# LD_driver.net
KiCad netlist of a schematic drawn in Altium Designer
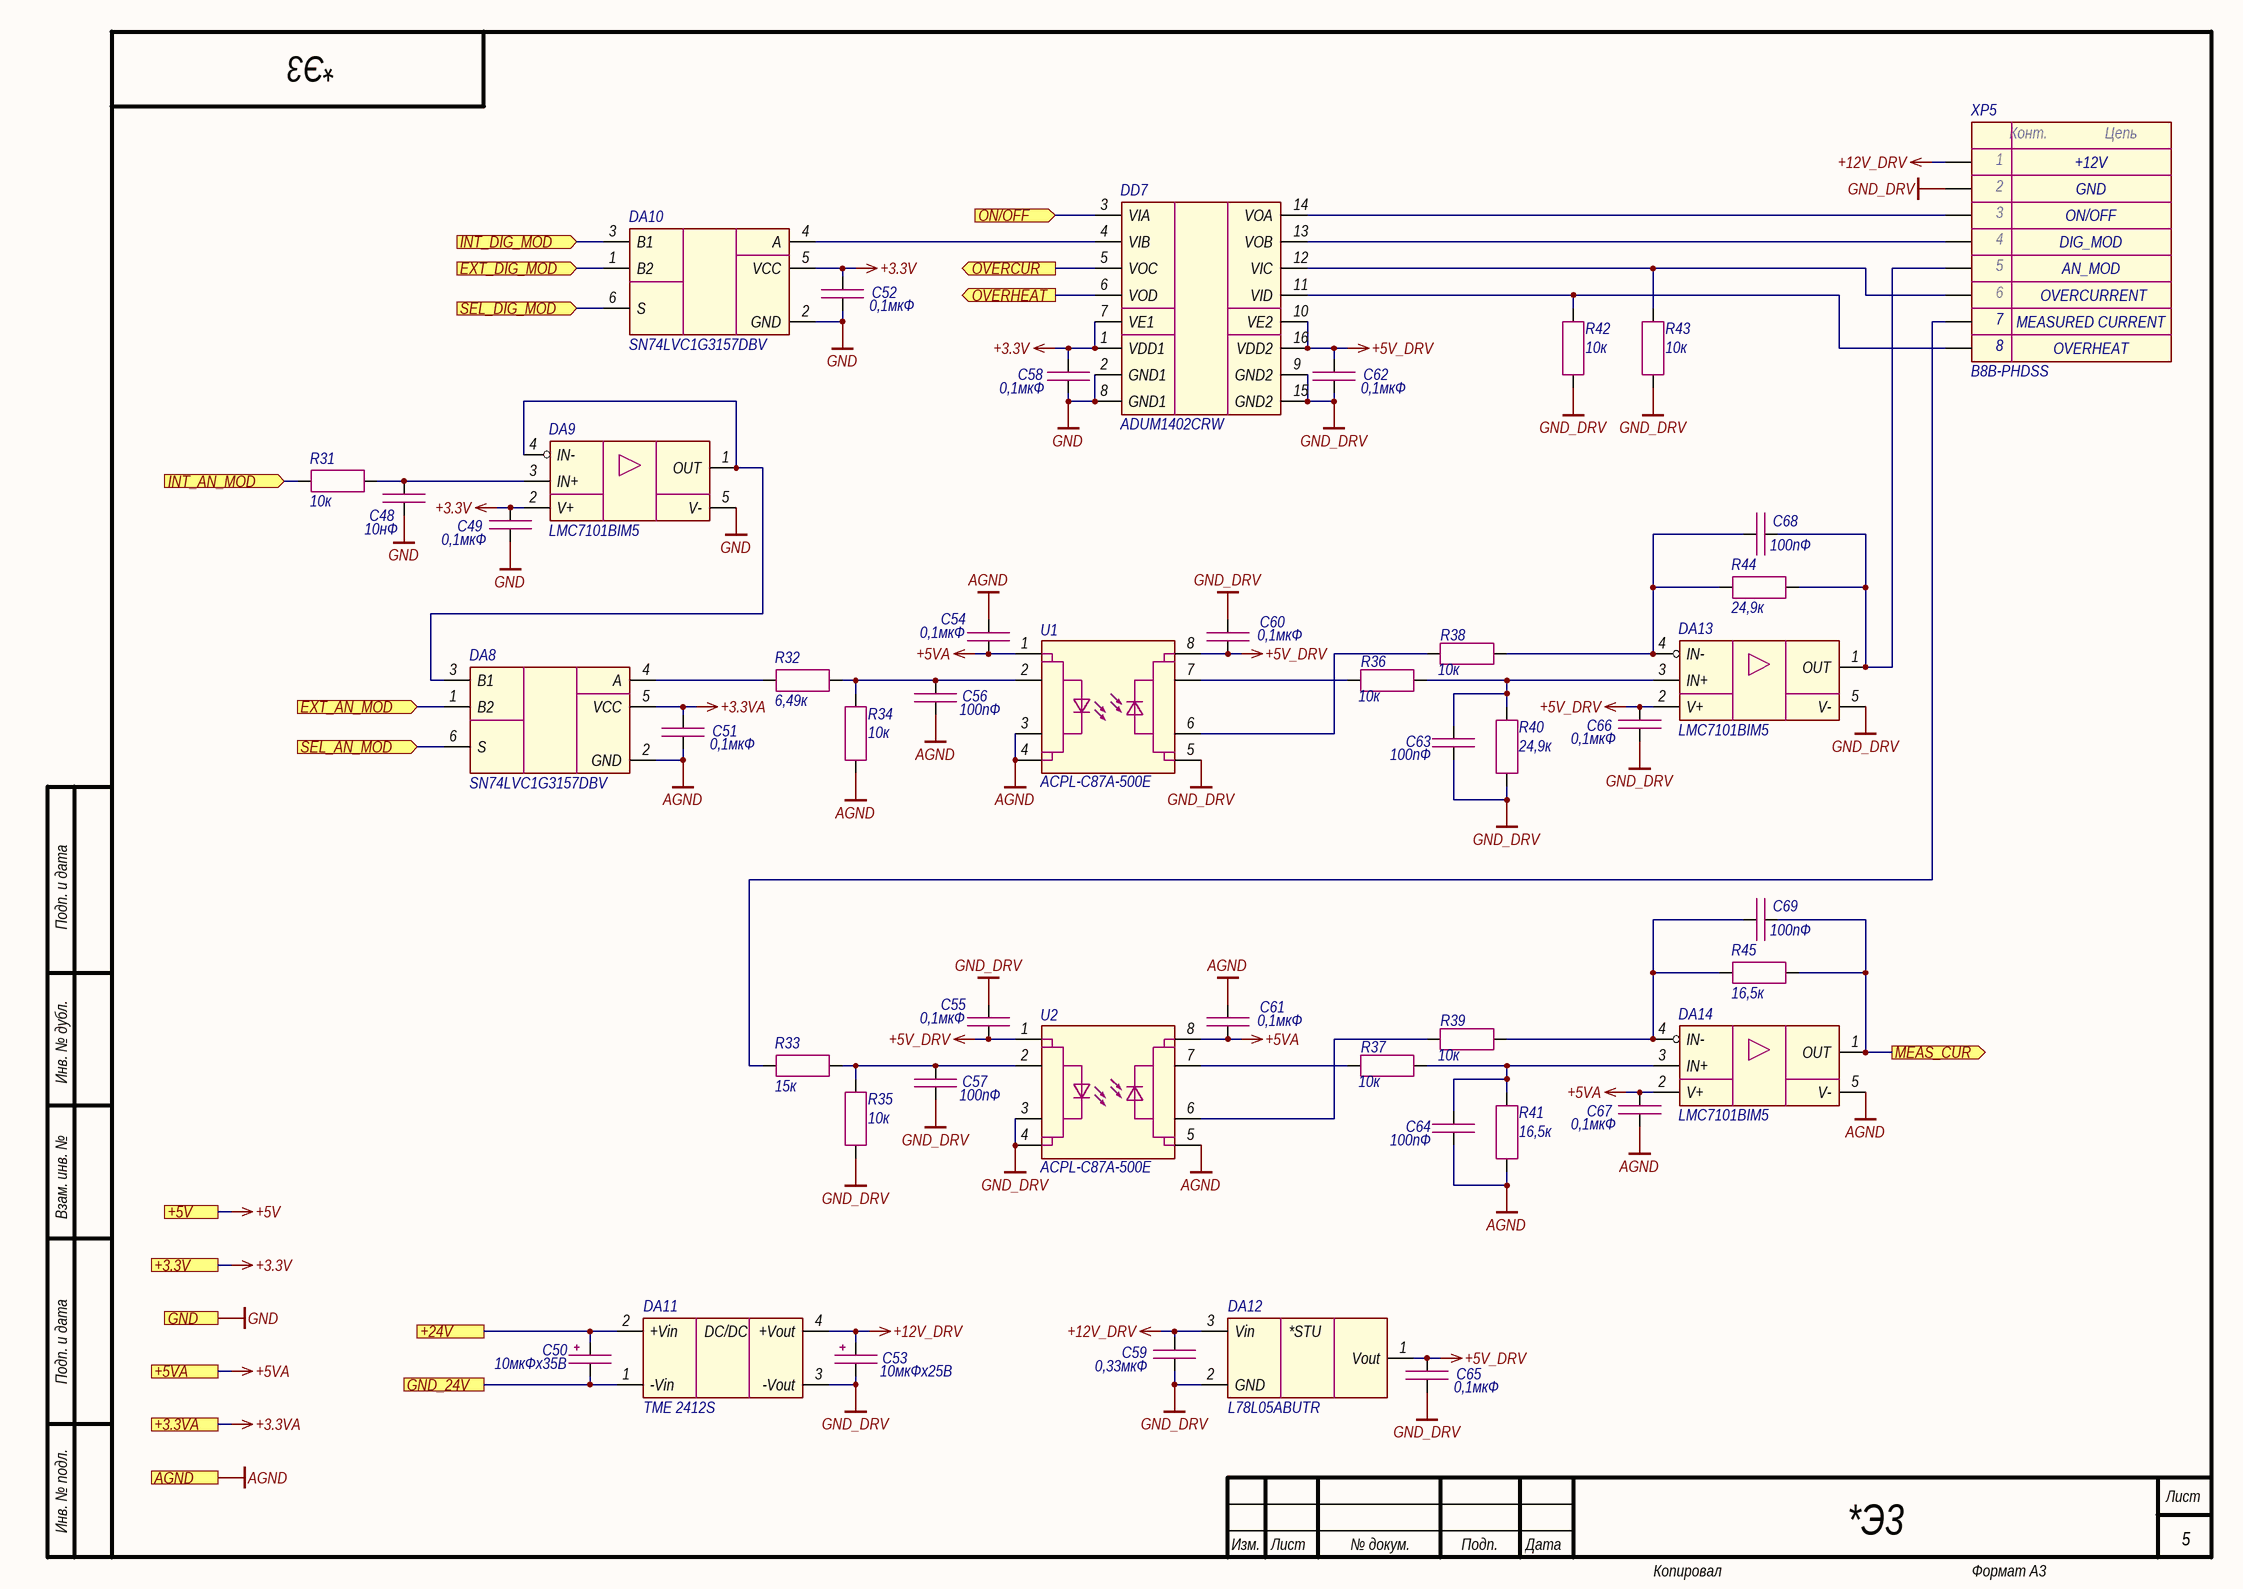
[diagram p0: LD_driver.SchDoc]

(export (version "E")
  (design (tool "Eeschema 10.0.6"))
  (components
    (comp (ref "C48")
      (value "10нФ")
      (footprint "Pcb_library:CAP_0603")
      (fields (field (name "MANUFACTURER") "Murata"))
      (libsource (lib "Schem_library") (part "Capacitor"))
    )
    (comp (ref "C49")
      (value "0,1мкФ")
      (footprint "Pcb_library:CAP_0603")
      (fields (field (name "MANUFACTURER") "Murata"))
      (libsource (lib "Schem_library") (part "Capacitor"))
    )
    (comp (ref "C50")
      (value "10мкФх35B")
      (footprint "Pcb_library:CAP_C")
      (libsource (lib "Schem_library") (part "Capacitor_Polar"))
    )
    (comp (ref "C51")
      (value "0,1мкФ")
      (footprint "Pcb_library:CAP_0603")
      (fields (field (name "MANUFACTURER") "Murata"))
      (libsource (lib "Schem_library") (part "Capacitor"))
    )
    (comp (ref "C52")
      (value "0,1мкФ")
      (footprint "Pcb_library:CAP_0603")
      (fields (field (name "MANUFACTURER") "Murata"))
      (libsource (lib "Schem_library") (part "Capacitor"))
    )
    (comp (ref "C53")
      (value "10мкФх25B")
      (footprint "Pcb_library:CAP_C")
      (libsource (lib "Schem_library") (part "Capacitor_Polar"))
    )
    (comp (ref "C54")
      (value "0,1мкФ")
      (footprint "Pcb_library:CAP_0603")
      (fields (field (name "MANUFACTURER") "Murata"))
      (libsource (lib "Schem_library") (part "Capacitor"))
    )
    (comp (ref "C55")
      (value "0,1мкФ")
      (footprint "Pcb_library:CAP_0603")
      (fields (field (name "MANUFACTURER") "Murata"))
      (libsource (lib "Schem_library") (part "Capacitor"))
    )
    (comp (ref "C56")
      (value "100пФ")
      (footprint "Pcb_library:CAP_0603")
      (fields (field (name "MANUFACTURER") "Murata"))
      (libsource (lib "Schem_library") (part "Capacitor"))
    )
    (comp (ref "C57")
      (value "100пФ")
      (footprint "Pcb_library:CAP_0603")
      (fields (field (name "MANUFACTURER") "Murata"))
      (libsource (lib "Schem_library") (part "Capacitor"))
    )
    (comp (ref "C58")
      (value "0,1мкФ")
      (footprint "Pcb_library:CAP_0603")
      (fields (field (name "MANUFACTURER") "Murata"))
      (libsource (lib "Schem_library") (part "Capacitor"))
    )
    (comp (ref "C59")
      (value "0,33мкФ")
      (footprint "Pcb_library:CAP_0805")
      (fields (field (name "MANUFACTURER") "Murata"))
      (libsource (lib "Schem_library") (part "Capacitor"))
    )
    (comp (ref "C60")
      (value "0,1мкФ")
      (footprint "Pcb_library:CAP_0603")
      (fields (field (name "MANUFACTURER") "Murata"))
      (libsource (lib "Schem_library") (part "Capacitor"))
    )
    (comp (ref "C61")
      (value "0,1мкФ")
      (footprint "Pcb_library:CAP_0603")
      (fields (field (name "MANUFACTURER") "Murata"))
      (libsource (lib "Schem_library") (part "Capacitor"))
    )
    (comp (ref "C62")
      (value "0,1мкФ")
      (footprint "Pcb_library:CAP_0603")
      (fields (field (name "MANUFACTURER") "Murata"))
      (libsource (lib "Schem_library") (part "Capacitor"))
    )
    (comp (ref "C63")
      (value "100пФ")
      (footprint "Pcb_library:CAP_0603")
      (fields (field (name "MANUFACTURER") "Murata"))
      (libsource (lib "Schem_library") (part "Capacitor"))
    )
    (comp (ref "C64")
      (value "100пФ")
      (footprint "Pcb_library:CAP_0603")
      (fields (field (name "MANUFACTURER") "Murata"))
      (libsource (lib "Schem_library") (part "Capacitor"))
    )
    (comp (ref "C65")
      (value "0,1мкФ")
      (footprint "Pcb_library:CAP_0603")
      (fields (field (name "MANUFACTURER") "Murata"))
      (libsource (lib "Schem_library") (part "Capacitor"))
    )
    (comp (ref "C66")
      (value "0,1мкФ")
      (footprint "Pcb_library:CAP_0603")
      (fields (field (name "MANUFACTURER") "Murata"))
      (libsource (lib "Schem_library") (part "Capacitor"))
    )
    (comp (ref "C67")
      (value "0,1мкФ")
      (footprint "Pcb_library:CAP_0603")
      (fields (field (name "MANUFACTURER") "Murata"))
      (libsource (lib "Schem_library") (part "Capacitor"))
    )
    (comp (ref "C68")
      (value "100пФ")
      (footprint "Pcb_library:CAP_0603")
      (fields (field (name "MANUFACTURER") "Murata"))
      (libsource (lib "Schem_library") (part "Capacitor"))
    )
    (comp (ref "C69")
      (value "100пФ")
      (footprint "Pcb_library:CAP_0603")
      (fields (field (name "MANUFACTURER") "Murata"))
      (libsource (lib "Schem_library") (part "Capacitor"))
    )
    (comp (ref "DA8")
      (value "SN74LVC1G3157DBV")
      (footprint "Pcb_library:SOT-23-6")
      (fields (field (name "MANUFACTURER") "Texas Instruments"))
      (libsource (lib "Schem_library") (part "SN74LVC1G3157"))
    )
    (comp (ref "DA9")
      (value "LMC7101BIM5")
      (footprint "Pcb_library:SOT-23-5")
      (fields (field (name "MANUFACTURER") "Texas Instruments"))
      (libsource (lib "Schem_library") (part "LMC7101"))
    )
    (comp (ref "DA10")
      (value "SN74LVC1G3157DBV")
      (footprint "Pcb_library:SOT-23-6")
      (fields (field (name "MANUFACTURER") "Texas Instruments"))
      (libsource (lib "Schem_library") (part "SN74LVC1G3157"))
    )
    (comp (ref "DA11")
      (value "TME 2412S")
      (footprint "Pcb_library:TME (SIP-4)")
      (fields (field (name "MANUFACTURER") "Traco Power"))
      (libsource (lib "Schem_library") (part "TME"))
    )
    (comp (ref "DA12")
      (value "L78L05ABUTR")
      (footprint "Pcb_library:SOT-89")
      (fields (field (name "MANUFACTURER") "STMicroelectronics"))
      (libsource (lib "Schem_library") (part "LD2981ABU50TR"))
    )
    (comp (ref "DA13")
      (value "LMC7101BIM5")
      (footprint "Pcb_library:SOT-23-5")
      (fields (field (name "MANUFACTURER") "Texas Instruments"))
      (libsource (lib "Schem_library") (part "LMC7101"))
    )
    (comp (ref "DA14")
      (value "LMC7101BIM5")
      (footprint "Pcb_library:SOT-23-5")
      (fields (field (name "MANUFACTURER") "Texas Instruments"))
      (libsource (lib "Schem_library") (part "LMC7101"))
    )
    (comp (ref "DD7")
      (value "ADUM1402CRW")
      (footprint "Pcb_library:SOIC-16W")
      (fields (field (name "MANUFACTURER") "Analog Devices"))
      (libsource (lib "Schem_library") (part "ADUM1402"))
    )
    (comp (ref "R31")
      (value "10к")
      (footprint "Pcb_library:RES_0603")
      (fields (field (name "MANUFACTURER") "Yageo"))
      (libsource (lib "Schem_library") (part "Resistor"))
    )
    (comp (ref "R32")
      (value "6,49к")
      (footprint "Pcb_library:RES_0603")
      (fields (field (name "MANUFACTURER") "Yageo"))
      (libsource (lib "Schem_library") (part "Resistor"))
    )
    (comp (ref "R33")
      (value "15к")
      (footprint "Pcb_library:RES_0603")
      (fields (field (name "MANUFACTURER") "Yageo"))
      (libsource (lib "Schem_library") (part "Resistor"))
    )
    (comp (ref "R34")
      (value "10к")
      (footprint "Pcb_library:RES_0603")
      (fields (field (name "MANUFACTURER") "Yageo"))
      (libsource (lib "Schem_library") (part "Resistor"))
    )
    (comp (ref "R35")
      (value "10к")
      (footprint "Pcb_library:RES_0603")
      (fields (field (name "MANUFACTURER") "Yageo"))
      (libsource (lib "Schem_library") (part "Resistor"))
    )
    (comp (ref "R36")
      (value "10к")
      (footprint "Pcb_library:RES_0603")
      (fields (field (name "MANUFACTURER") "Yageo"))
      (libsource (lib "Schem_library") (part "Resistor"))
    )
    (comp (ref "R37")
      (value "10к")
      (footprint "Pcb_library:RES_0603")
      (fields (field (name "MANUFACTURER") "Yageo"))
      (libsource (lib "Schem_library") (part "Resistor"))
    )
    (comp (ref "R38")
      (value "10к")
      (footprint "Pcb_library:RES_0603")
      (fields (field (name "MANUFACTURER") "Yageo"))
      (libsource (lib "Schem_library") (part "Resistor"))
    )
    (comp (ref "R39")
      (value "10к")
      (footprint "Pcb_library:RES_0603")
      (fields (field (name "MANUFACTURER") "Yageo"))
      (libsource (lib "Schem_library") (part "Resistor"))
    )
    (comp (ref "R40")
      (value "24,9к")
      (footprint "Pcb_library:RES_0603")
      (fields (field (name "MANUFACTURER") "Yageo"))
      (libsource (lib "Schem_library") (part "Resistor"))
    )
    (comp (ref "R41")
      (value "16,5к")
      (footprint "Pcb_library:RES_0603")
      (fields (field (name "MANUFACTURER") "Yageo"))
      (libsource (lib "Schem_library") (part "Resistor"))
    )
    (comp (ref "R42")
      (value "10к")
      (footprint "Pcb_library:RES_0603")
      (fields (field (name "MANUFACTURER") "Yageo"))
      (libsource (lib "Schem_library") (part "Resistor"))
    )
    (comp (ref "R43")
      (value "10к")
      (footprint "Pcb_library:RES_0603")
      (fields (field (name "MANUFACTURER") "Yageo"))
      (libsource (lib "Schem_library") (part "Resistor"))
    )
    (comp (ref "R44")
      (value "24,9к")
      (footprint "Pcb_library:RES_0603")
      (fields (field (name "MANUFACTURER") "Yageo"))
      (libsource (lib "Schem_library") (part "Resistor"))
    )
    (comp (ref "R45")
      (value "16,5к")
      (footprint "Pcb_library:RES_0603")
      (fields (field (name "MANUFACTURER") "Yageo"))
      (libsource (lib "Schem_library") (part "Resistor"))
    )
    (comp (ref "U1")
      (value "ACPL-C87A-500E")
      (footprint "Pcb_library:SSO-8")
      (fields (field (name "MANUFACTURER") "Broadcom"))
      (libsource (lib "Schem_library") (part "ACPL-C87"))
    )
    (comp (ref "U2")
      (value "ACPL-C87A-500E")
      (footprint "Pcb_library:SSO-8")
      (fields (field (name "MANUFACTURER") "Broadcom"))
      (libsource (lib "Schem_library") (part "ACPL-C87"))
    )
    (comp (ref "XP5")
      (value "B8B-PHDSS")
      (footprint "Pcb_library:B8B-PHDSS")
      (fields (field (name "MANUFACTURER") "JST"))
      (libsource (lib "Schem_library") (part "Connector-8"))
    )
  )
  (nets
    (net (code "1") (name "+3.3V") (class "Default")
      (node (ref "C49") (pin "1") (pinfunction "1_1") (pintype "passive"))
      (node (ref "C52") (pin "1") (pinfunction "1_1") (pintype "passive"))
      (node (ref "C58") (pin "1") (pinfunction "1_1") (pintype "passive"))
      (node (ref "DA10") (pin "5") (pinfunction "VCC_5") (pintype "passive"))
      (node (ref "DA9") (pin "2") (pinfunction "V+_2") (pintype "passive"))
      (node (ref "DD7") (pin "1") (pinfunction "VDD1_1") (pintype "passive"))
      (node (ref "DD7") (pin "7") (pinfunction "VE1_7") (pintype "passive"))
    )
    (net (code "2") (name "+3.3VA") (class "Default")
      (node (ref "C51") (pin "1") (pinfunction "1_1") (pintype "passive"))
      (node (ref "DA8") (pin "5") (pinfunction "VCC_5") (pintype "passive"))
    )
    (net (code "4") (name "+5VA") (class "Default")
      (node (ref "C54") (pin "1") (pinfunction "1_1") (pintype "passive"))
      (node (ref "C61") (pin "1") (pinfunction "1_1") (pintype "passive"))
      (node (ref "C67") (pin "1") (pinfunction "1_1") (pintype "passive"))
      (node (ref "DA14") (pin "2") (pinfunction "V+_2") (pintype "passive"))
      (node (ref "U1") (pin "1") (pinfunction "VDD1_1") (pintype "passive"))
      (node (ref "U2") (pin "8") (pinfunction "VDD2_8") (pintype "passive"))
    )
    (net (code "5") (name "+5V_DRV") (class "Default")
      (node (ref "C55") (pin "1") (pinfunction "1_1") (pintype "passive"))
      (node (ref "C60") (pin "1") (pinfunction "1_1") (pintype "passive"))
      (node (ref "C62") (pin "1") (pinfunction "1_1") (pintype "passive"))
      (node (ref "C65") (pin "1") (pinfunction "1_1") (pintype "passive"))
      (node (ref "C66") (pin "1") (pinfunction "1_1") (pintype "passive"))
      (node (ref "DA12") (pin "1") (pinfunction "Vout_1") (pintype "passive"))
      (node (ref "DA13") (pin "2") (pinfunction "V+_2") (pintype "passive"))
      (node (ref "DD7") (pin "10") (pinfunction "VE2_10") (pintype "passive"))
      (node (ref "DD7") (pin "16") (pinfunction "VDD2_16") (pintype "passive"))
      (node (ref "U1") (pin "8") (pinfunction "VDD2_8") (pintype "passive"))
      (node (ref "U2") (pin "1") (pinfunction "VDD1_1") (pintype "passive"))
    )
    (net (code "6") (name "+12V_DRV") (class "Default")
      (node (ref "C53") (pin "1") (pinfunction "1_1") (pintype "passive"))
      (node (ref "C59") (pin "2") (pinfunction "2_2") (pintype "passive"))
      (node (ref "DA11") (pin "4") (pinfunction "+Vout_4") (pintype "passive"))
      (node (ref "DA12") (pin "3") (pinfunction "Vin_3") (pintype "passive"))
      (node (ref "XP5") (pin "1") (pintype "passive"))
    )
    (net (code "7") (name "/+24V") (class "Default")
      (node (ref "C50") (pin "1") (pinfunction "1_1") (pintype "passive"))
      (node (ref "DA11") (pin "2") (pinfunction "+Vin_2") (pintype "passive"))
    )
    (net (code "8") (name "/EXT_AN_MOD") (class "Default")
      (node (ref "DA8") (pin "1") (pinfunction "B2_1") (pintype "passive"))
    )
    (net (code "9") (name "/EXT_DIG_MOD") (class "Default")
      (node (ref "DA10") (pin "1") (pinfunction "B2_1") (pintype "passive"))
    )
    (net (code "10") (name "/GND_24V") (class "Default")
      (node (ref "C50") (pin "2") (pinfunction "2_2") (pintype "passive"))
      (node (ref "DA11") (pin "1") (pinfunction "-Vin_1") (pintype "passive"))
    )
    (net (code "11") (name "/INT_AN_MOD") (class "Default")
      (node (ref "R31") (pin "1") (pinfunction "1_1") (pintype "passive"))
    )
    (net (code "12") (name "/INT_DIG_MOD") (class "Default")
      (node (ref "DA10") (pin "3") (pinfunction "B1_3") (pintype "passive"))
    )
    (net (code "13") (name "/MEAS_CUR") (class "Default")
      (node (ref "C69") (pin "2") (pinfunction "2_2") (pintype "passive"))
      (node (ref "DA14") (pin "1") (pinfunction "OUT_1") (pintype "passive"))
      (node (ref "R45") (pin "1") (pinfunction "1_1") (pintype "passive"))
    )
    (net (code "14") (name "/ON{slash}OFF") (class "Default")
      (node (ref "DD7") (pin "3") (pinfunction "VIA_3") (pintype "passive"))
    )
    (net (code "15") (name "/OVERCUR") (class "Default")
      (node (ref "DD7") (pin "5") (pinfunction "VOC_5") (pintype "passive"))
    )
    (net (code "16") (name "/OVERHEAT") (class "Default")
      (node (ref "DD7") (pin "6") (pinfunction "VOD_6") (pintype "passive"))
    )
    (net (code "17") (name "/SEL_AN_MOD") (class "Default")
      (node (ref "DA8") (pin "6") (pinfunction "S_6") (pintype "passive"))
    )
    (net (code "18") (name "/SEL_DIG_MOD") (class "Default")
      (node (ref "DA10") (pin "6") (pinfunction "S_6") (pintype "passive"))
    )
    (net (code "19") (name "AGND") (class "Default")
      (node (ref "C51") (pin "2") (pinfunction "2_2") (pintype "passive"))
      (node (ref "C54") (pin "2") (pinfunction "2_2") (pintype "passive"))
      (node (ref "C56") (pin "1") (pinfunction "1_1") (pintype "passive"))
      (node (ref "C61") (pin "2") (pinfunction "2_2") (pintype "passive"))
      (node (ref "C64") (pin "2") (pinfunction "2_2") (pintype "passive"))
      (node (ref "C67") (pin "2") (pinfunction "2_2") (pintype "passive"))
      (node (ref "DA14") (pin "5") (pinfunction "V-_5") (pintype "passive"))
      (node (ref "DA8") (pin "2") (pinfunction "GND_2") (pintype "passive"))
      (node (ref "R34") (pin "2") (pinfunction "2_2") (pintype "passive"))
      (node (ref "R41") (pin "2") (pinfunction "2_2") (pintype "passive"))
      (node (ref "U1") (pin "3") (pinfunction "SHDN_3") (pintype "passive"))
      (node (ref "U1") (pin "4") (pinfunction "GND1_4") (pintype "passive"))
      (node (ref "U2") (pin "5") (pinfunction "GND2_5") (pintype "passive"))
    )
    (net (code "20") (name "GND") (class "Default")
      (node (ref "C48") (pin "2") (pinfunction "2_2") (pintype "passive"))
      (node (ref "C49") (pin "2") (pinfunction "2_2") (pintype "passive"))
      (node (ref "C52") (pin "2") (pinfunction "2_2") (pintype "passive"))
      (node (ref "C58") (pin "2") (pinfunction "2_2") (pintype "passive"))
      (node (ref "DA10") (pin "2") (pinfunction "GND_2") (pintype "passive"))
      (node (ref "DA9") (pin "5") (pinfunction "V-_5") (pintype "passive"))
      (node (ref "DD7") (pin "2") (pinfunction "GND1_2") (pintype "passive"))
      (node (ref "DD7") (pin "8") (pinfunction "GND1_8") (pintype "passive"))
    )
    (net (code "21") (name "GND_DRV") (class "Default")
      (node (ref "C53") (pin "2") (pinfunction "2_2") (pintype "passive"))
      (node (ref "C55") (pin "2") (pinfunction "2_2") (pintype "passive"))
      (node (ref "C57") (pin "1") (pinfunction "1_1") (pintype "passive"))
      (node (ref "C59") (pin "1") (pinfunction "1_1") (pintype "passive"))
      (node (ref "C60") (pin "2") (pinfunction "2_2") (pintype "passive"))
      (node (ref "C62") (pin "2") (pinfunction "2_2") (pintype "passive"))
      (node (ref "C63") (pin "2") (pinfunction "2_2") (pintype "passive"))
      (node (ref "C65") (pin "2") (pinfunction "2_2") (pintype "passive"))
      (node (ref "C66") (pin "2") (pinfunction "2_2") (pintype "passive"))
      (node (ref "DA11") (pin "3") (pinfunction "-Vout_3") (pintype "passive"))
      (node (ref "DA12") (pin "2") (pinfunction "GND_2") (pintype "passive"))
      (node (ref "DA13") (pin "5") (pinfunction "V-_5") (pintype "passive"))
      (node (ref "DD7") (pin "15") (pinfunction "GND2_15") (pintype "passive"))
      (node (ref "DD7") (pin "9") (pinfunction "GND2_9") (pintype "passive"))
      (node (ref "R35") (pin "2") (pinfunction "2_2") (pintype "passive"))
      (node (ref "R40") (pin "1") (pinfunction "1_1") (pintype "passive"))
      (node (ref "R42") (pin "2") (pinfunction "2_2") (pintype "passive"))
      (node (ref "R43") (pin "2") (pinfunction "2_2") (pintype "passive"))
      (node (ref "U1") (pin "5") (pinfunction "GND2_5") (pintype "passive"))
      (node (ref "U2") (pin "3") (pinfunction "SHDN_3") (pintype "passive"))
      (node (ref "U2") (pin "4") (pinfunction "GND1_4") (pintype "passive"))
      (node (ref "XP5") (pin "2") (pintype "passive"))
    )
    (net (code "22") (name "Net-(DA8-A)") (class "Default")
      (node (ref "DA8") (pin "4") (pinfunction "A_4") (pintype "passive"))
      (node (ref "R32") (pin "2") (pinfunction "2_2") (pintype "passive"))
    )
    (net (code "23") (name "Net-(DA8-B1)") (class "Default")
      (node (ref "DA8") (pin "3") (pinfunction "B1_3") (pintype "passive"))
      (node (ref "DA9") (pin "1") (pinfunction "OUT_1") (pintype "passive"))
      (node (ref "DA9") (pin "4") (pinfunction "IN-_4") (pintype "passive"))
    )
    (net (code "24") (name "Net-(DA9-IN+)") (class "Default")
      (node (ref "C48") (pin "1") (pinfunction "1_1") (pintype "passive"))
      (node (ref "DA9") (pin "3") (pinfunction "IN+_3") (pintype "passive"))
      (node (ref "R31") (pin "2") (pinfunction "2_2") (pintype "passive"))
    )
    (net (code "25") (name "Net-(DA10-A)") (class "Default")
      (node (ref "DA10") (pin "4") (pinfunction "A_4") (pintype "passive"))
      (node (ref "DD7") (pin "4") (pinfunction "VIB_4") (pintype "passive"))
    )
    (net (code "26") (name "Net-(DA13-IN+)") (class "Default")
      (node (ref "C63") (pin "1") (pinfunction "1_1") (pintype "passive"))
      (node (ref "DA13") (pin "3") (pinfunction "IN+_3") (pintype "passive"))
      (node (ref "R36") (pin "2") (pinfunction "2_2") (pintype "passive"))
      (node (ref "R40") (pin "2") (pinfunction "2_2") (pintype "passive"))
    )
    (net (code "27") (name "Net-(DA13-IN-)") (class "Default")
      (node (ref "C68") (pin "1") (pinfunction "1_1") (pintype "passive"))
      (node (ref "DA13") (pin "4") (pinfunction "IN-_4") (pintype "passive"))
      (node (ref "R38") (pin "2") (pinfunction "2_2") (pintype "passive"))
      (node (ref "R44") (pin "1") (pinfunction "1_1") (pintype "passive"))
    )
    (net (code "28") (name "Net-(DA13-OUT)") (class "Default")
      (node (ref "C68") (pin "2") (pinfunction "2_2") (pintype "passive"))
      (node (ref "DA13") (pin "1") (pinfunction "OUT_1") (pintype "passive"))
      (node (ref "R44") (pin "2") (pinfunction "2_2") (pintype "passive"))
      (node (ref "XP5") (pin "5") (pintype "passive"))
    )
    (net (code "29") (name "Net-(DA14-IN+)") (class "Default")
      (node (ref "C64") (pin "1") (pinfunction "1_1") (pintype "passive"))
      (node (ref "DA14") (pin "3") (pinfunction "IN+_3") (pintype "passive"))
      (node (ref "R37") (pin "2") (pinfunction "2_2") (pintype "passive"))
      (node (ref "R41") (pin "1") (pinfunction "1_1") (pintype "passive"))
    )
    (net (code "30") (name "Net-(DA14-IN-)") (class "Default")
      (node (ref "C69") (pin "1") (pinfunction "1_1") (pintype "passive"))
      (node (ref "DA14") (pin "4") (pinfunction "IN-_4") (pintype "passive"))
      (node (ref "R39") (pin "2") (pinfunction "2_2") (pintype "passive"))
      (node (ref "R45") (pin "2") (pinfunction "2_2") (pintype "passive"))
    )
    (net (code "31") (name "Net-(DD7-VIC)") (class "Default")
      (node (ref "DD7") (pin "12") (pinfunction "VIC_12") (pintype "passive"))
      (node (ref "R43") (pin "1") (pinfunction "1_1") (pintype "passive"))
      (node (ref "XP5") (pin "6") (pintype "passive"))
    )
    (net (code "32") (name "Net-(DD7-VID)") (class "Default")
      (node (ref "DD7") (pin "11") (pinfunction "VID_11") (pintype "passive"))
      (node (ref "R42") (pin "1") (pinfunction "1_1") (pintype "passive"))
      (node (ref "XP5") (pin "8") (pintype "passive"))
    )
    (net (code "33") (name "Net-(DD7-VOA)") (class "Default")
      (node (ref "DD7") (pin "14") (pinfunction "VOA_14") (pintype "passive"))
      (node (ref "XP5") (pin "3") (pintype "passive"))
    )
    (net (code "34") (name "Net-(DD7-VOB)") (class "Default")
      (node (ref "DD7") (pin "13") (pinfunction "VOB_13") (pintype "passive"))
      (node (ref "XP5") (pin "4") (pintype "passive"))
    )
    (net (code "35") (name "Net-(R33-Pad2)") (class "Default")
      (node (ref "R33") (pin "2") (pinfunction "2_2") (pintype "passive"))
      (node (ref "XP5") (pin "7") (pintype "passive"))
    )
    (net (code "36") (name "Net-(U1-VIN)") (class "Default")
      (node (ref "C56") (pin "2") (pinfunction "2_2") (pintype "passive"))
      (node (ref "R32") (pin "1") (pinfunction "1_1") (pintype "passive"))
      (node (ref "R34") (pin "1") (pinfunction "1_1") (pintype "passive"))
      (node (ref "U1") (pin "2") (pinfunction "VIN_2") (pintype "passive"))
    )
    (net (code "37") (name "Net-(U1-VOUT+)") (class "Default")
      (node (ref "R36") (pin "1") (pinfunction "1_1") (pintype "passive"))
      (node (ref "U1") (pin "7") (pinfunction "VOUT+_7") (pintype "passive"))
    )
    (net (code "38") (name "Net-(U1-VOUT-)") (class "Default")
      (node (ref "R38") (pin "1") (pinfunction "1_1") (pintype "passive"))
      (node (ref "U1") (pin "6") (pinfunction "VOUT-_6") (pintype "passive"))
    )
    (net (code "39") (name "Net-(U2-VIN)") (class "Default")
      (node (ref "C57") (pin "2") (pinfunction "2_2") (pintype "passive"))
      (node (ref "R33") (pin "1") (pinfunction "1_1") (pintype "passive"))
      (node (ref "R35") (pin "1") (pinfunction "1_1") (pintype "passive"))
      (node (ref "U2") (pin "2") (pinfunction "VIN_2") (pintype "passive"))
    )
    (net (code "40") (name "Net-(U2-VOUT+)") (class "Default")
      (node (ref "R37") (pin "1") (pinfunction "1_1") (pintype "passive"))
      (node (ref "U2") (pin "7") (pinfunction "VOUT+_7") (pintype "passive"))
    )
    (net (code "41") (name "Net-(U2-VOUT-)") (class "Default")
      (node (ref "R39") (pin "1") (pinfunction "1_1") (pintype "passive"))
      (node (ref "U2") (pin "6") (pinfunction "VOUT-_6") (pintype "passive"))
    )
  )
)
